# hardware-crackme.net
KiCad netlist of a schematic drawn in EAGLE
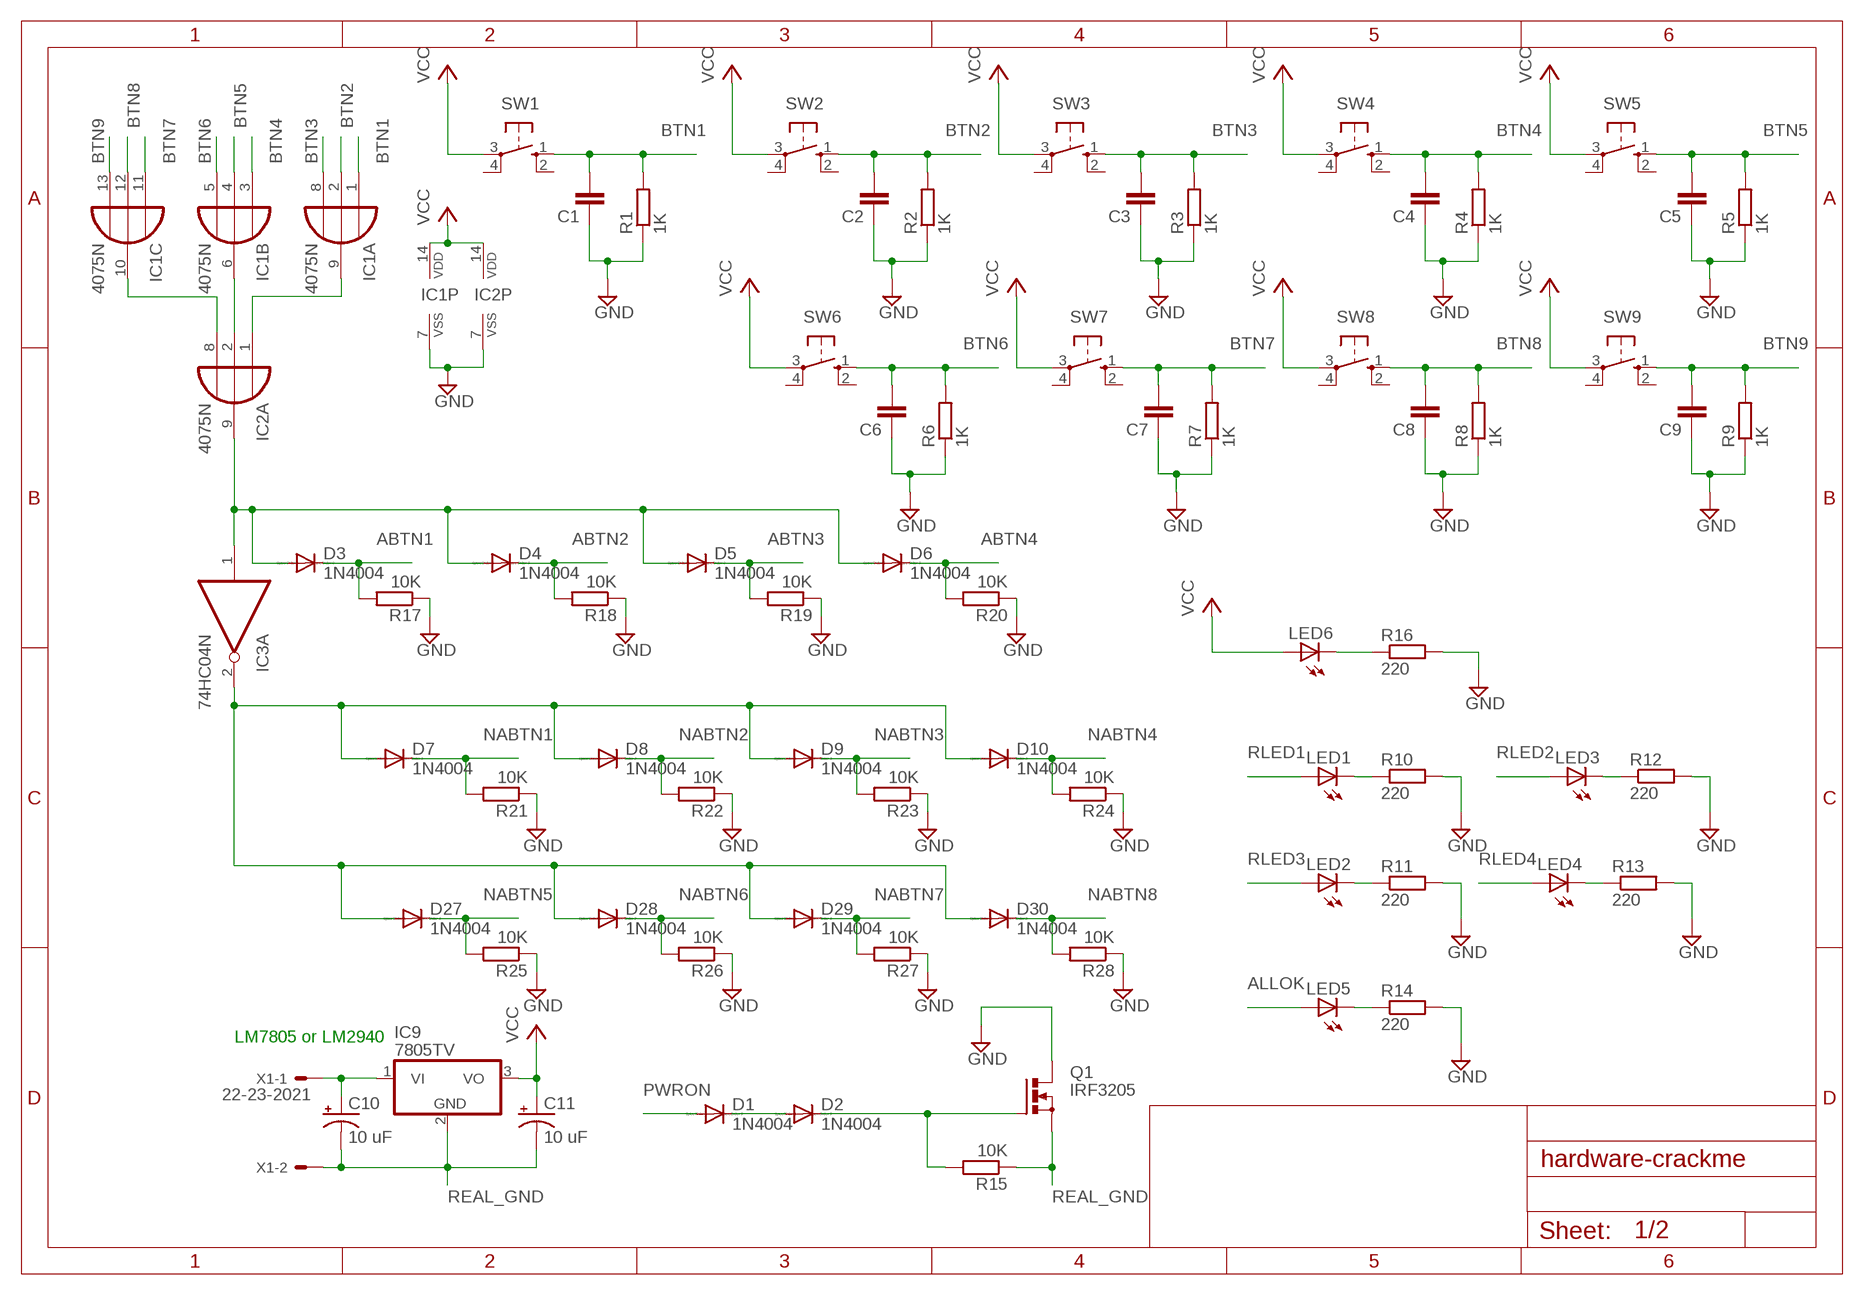
[diagram p0: schematic, sheet 1]
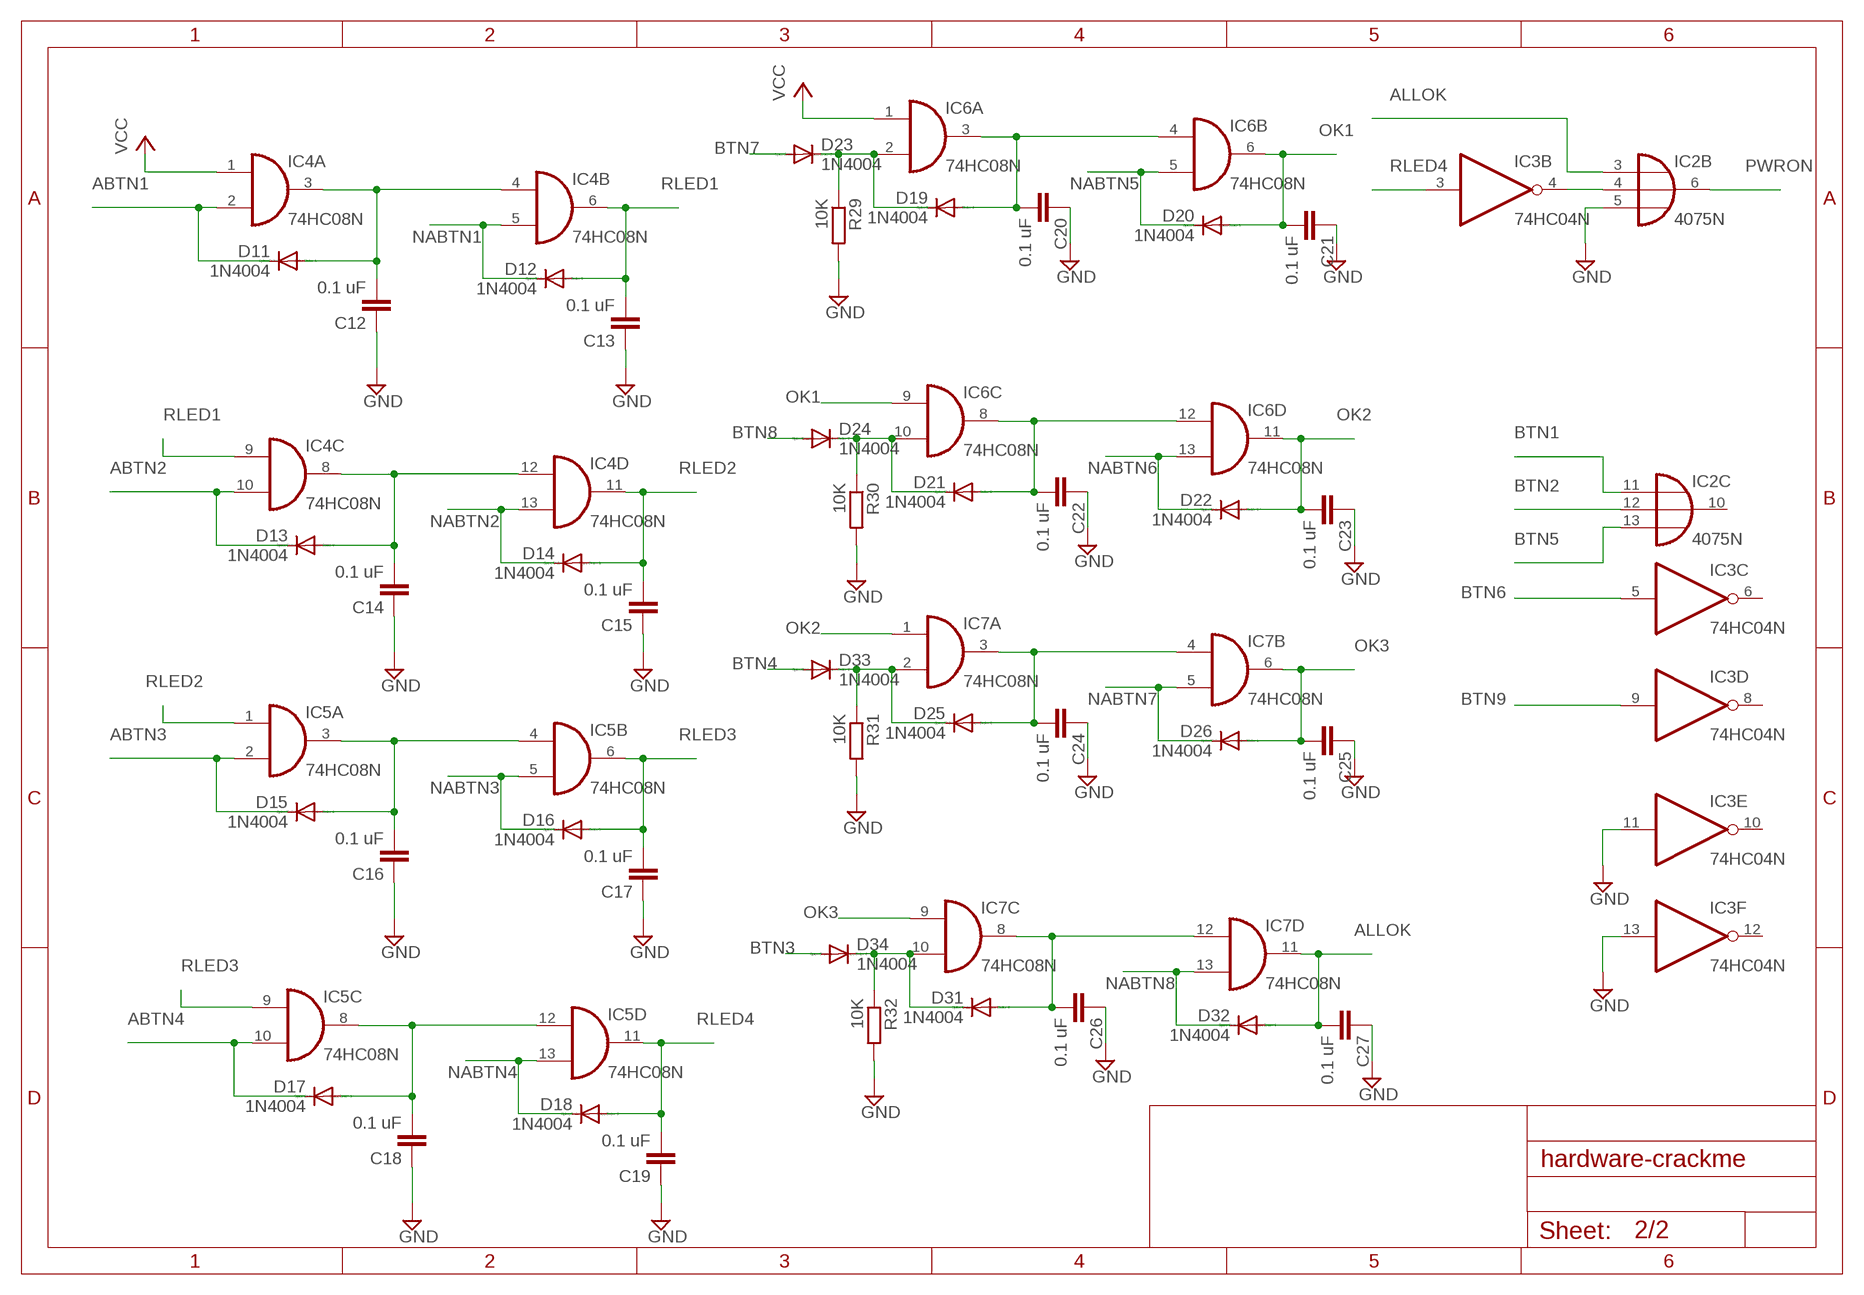
[diagram p1: schematic, sheet 2]

(export (version "E")
  (design (tool "Eeschema 10.0.6"))
  (components
    (comp (ref "C12")
      (value "0.1 uF")
      (footprint "eagle-import:C050-025X075")
      (libsource (lib "eagle-import") (part "C-EU050-025X075"))
    )
    (comp (ref "C13")
      (value "0.1 uF")
      (footprint "eagle-import:C050-025X075")
      (libsource (lib "eagle-import") (part "C-EU050-025X075"))
    )
    (comp (ref "C14")
      (value "0.1 uF")
      (footprint "eagle-import:C050-025X075")
      (libsource (lib "eagle-import") (part "C-EU050-025X075"))
    )
    (comp (ref "C15")
      (value "0.1 uF")
      (footprint "eagle-import:C050-025X075")
      (libsource (lib "eagle-import") (part "C-EU050-025X075"))
    )
    (comp (ref "C16")
      (value "0.1 uF")
      (footprint "eagle-import:C050-025X075")
      (libsource (lib "eagle-import") (part "C-EU050-025X075"))
    )
    (comp (ref "C17")
      (value "0.1 uF")
      (footprint "eagle-import:C050-025X075")
      (libsource (lib "eagle-import") (part "C-EU050-025X075"))
    )
    (comp (ref "C18")
      (value "0.1 uF")
      (footprint "eagle-import:C050-025X075")
      (libsource (lib "eagle-import") (part "C-EU050-025X075"))
    )
    (comp (ref "C19")
      (value "0.1 uF")
      (footprint "eagle-import:C050-025X075")
      (libsource (lib "eagle-import") (part "C-EU050-025X075"))
    )
    (comp (ref "C20")
      (value "0.1 uF")
      (footprint "eagle-import:C050-025X075")
      (libsource (lib "eagle-import") (part "C-EU050-025X075"))
    )
    (comp (ref "C21")
      (value "0.1 uF")
      (footprint "eagle-import:C050-025X075")
      (libsource (lib "eagle-import") (part "C-EU050-025X075"))
    )
    (comp (ref "C22")
      (value "0.1 uF")
      (footprint "eagle-import:C050-025X075")
      (libsource (lib "eagle-import") (part "C-EU050-025X075"))
    )
    (comp (ref "C23")
      (value "0.1 uF")
      (footprint "eagle-import:C050-025X075")
      (libsource (lib "eagle-import") (part "C-EU050-025X075"))
    )
    (comp (ref "C24")
      (value "0.1 uF")
      (footprint "eagle-import:C050-025X075")
      (libsource (lib "eagle-import") (part "C-EU050-025X075"))
    )
    (comp (ref "C25")
      (value "0.1 uF")
      (footprint "eagle-import:C050-025X075")
      (libsource (lib "eagle-import") (part "C-EU050-025X075"))
    )
    (comp (ref "C26")
      (value "0.1 uF")
      (footprint "eagle-import:C050-025X075")
      (libsource (lib "eagle-import") (part "C-EU050-025X075"))
    )
    (comp (ref "C27")
      (value "0.1 uF")
      (footprint "eagle-import:C050-025X075")
      (libsource (lib "eagle-import") (part "C-EU050-025X075"))
    )
    (comp (ref "D11")
      (value "1N4004")
      (footprint "eagle-import:DO41-10")
      (libsource (lib "eagle-import") (part "1N4004"))
    )
    (comp (ref "D12")
      (value "1N4004")
      (footprint "eagle-import:DO41-10")
      (libsource (lib "eagle-import") (part "1N4004"))
    )
    (comp (ref "D13")
      (value "1N4004")
      (footprint "eagle-import:DO41-10")
      (libsource (lib "eagle-import") (part "1N4004"))
    )
    (comp (ref "D14")
      (value "1N4004")
      (footprint "eagle-import:DO41-10")
      (libsource (lib "eagle-import") (part "1N4004"))
    )
    (comp (ref "D15")
      (value "1N4004")
      (footprint "eagle-import:DO41-10")
      (libsource (lib "eagle-import") (part "1N4004"))
    )
    (comp (ref "D16")
      (value "1N4004")
      (footprint "eagle-import:DO41-10")
      (libsource (lib "eagle-import") (part "1N4004"))
    )
    (comp (ref "D17")
      (value "1N4004")
      (footprint "eagle-import:DO41-10")
      (libsource (lib "eagle-import") (part "1N4004"))
    )
    (comp (ref "D18")
      (value "1N4004")
      (footprint "eagle-import:DO41-10")
      (libsource (lib "eagle-import") (part "1N4004"))
    )
    (comp (ref "D19")
      (value "1N4004")
      (footprint "eagle-import:DO41-10")
      (libsource (lib "eagle-import") (part "1N4004"))
    )
    (comp (ref "D20")
      (value "1N4004")
      (footprint "eagle-import:DO41-10")
      (libsource (lib "eagle-import") (part "1N4004"))
    )
    (comp (ref "D21")
      (value "1N4004")
      (footprint "eagle-import:DO41-10")
      (libsource (lib "eagle-import") (part "1N4004"))
    )
    (comp (ref "D22")
      (value "1N4004")
      (footprint "eagle-import:DO41-10")
      (libsource (lib "eagle-import") (part "1N4004"))
    )
    (comp (ref "D23")
      (value "1N4004")
      (footprint "eagle-import:DO41-10")
      (libsource (lib "eagle-import") (part "1N4004"))
    )
    (comp (ref "D24")
      (value "1N4004")
      (footprint "eagle-import:DO41-10")
      (libsource (lib "eagle-import") (part "1N4004"))
    )
    (comp (ref "D25")
      (value "1N4004")
      (footprint "eagle-import:DO41-10")
      (libsource (lib "eagle-import") (part "1N4004"))
    )
    (comp (ref "D26")
      (value "1N4004")
      (footprint "eagle-import:DO41-10")
      (libsource (lib "eagle-import") (part "1N4004"))
    )
    (comp (ref "D31")
      (value "1N4004")
      (footprint "eagle-import:DO41-10")
      (libsource (lib "eagle-import") (part "1N4004"))
    )
    (comp (ref "D32")
      (value "1N4004")
      (footprint "eagle-import:DO41-10")
      (libsource (lib "eagle-import") (part "1N4004"))
    )
    (comp (ref "D33")
      (value "1N4004")
      (footprint "eagle-import:DO41-10")
      (libsource (lib "eagle-import") (part "1N4004"))
    )
    (comp (ref "D34")
      (value "1N4004")
      (footprint "eagle-import:DO41-10")
      (libsource (lib "eagle-import") (part "1N4004"))
    )
    (comp (ref "IC2")
      (value "4075N")
      (footprint "eagle-import:DIL14")
      (libsource (lib "eagle-import") (part "4075N"))
    )
    (comp (ref "IC3")
      (value "74HC04N")
      (footprint "eagle-import:DIL14")
      (libsource (lib "eagle-import") (part "7404NHC"))
    )
    (comp (ref "IC4")
      (value "74HC08N")
      (footprint "eagle-import:DIL14")
      (libsource (lib "eagle-import") (part "7408NHC"))
    )
    (comp (ref "IC5")
      (value "74HC08N")
      (footprint "eagle-import:DIL14")
      (libsource (lib "eagle-import") (part "7408NHC"))
    )
    (comp (ref "IC6")
      (value "74HC08N")
      (footprint "eagle-import:DIL14")
      (libsource (lib "eagle-import") (part "7408NHC"))
    )
    (comp (ref "IC7")
      (value "74HC08N")
      (footprint "eagle-import:DIL14")
      (libsource (lib "eagle-import") (part "7408NHC"))
    )
    (comp (ref "R29")
      (value "10K")
      (footprint "eagle-import:0207_7")
      (libsource (lib "eagle-import") (part "R-EU_0207/7"))
    )
    (comp (ref "R30")
      (value "10K")
      (footprint "eagle-import:0207_7")
      (libsource (lib "eagle-import") (part "R-EU_0207/7"))
    )
    (comp (ref "R31")
      (value "10K")
      (footprint "eagle-import:0207_7")
      (libsource (lib "eagle-import") (part "R-EU_0207/7"))
    )
    (comp (ref "R32")
      (value "10K")
      (footprint "eagle-import:0207_7")
      (libsource (lib "eagle-import") (part "R-EU_0207/7"))
    )
    (comp (ref "C1")
      (value "C-EU050-025X075")
      (footprint "eagle-import:C050-025X075")
      (libsource (lib "eagle-import") (part "C-EU050-025X075"))
    )
    (comp (ref "C2")
      (value "C-EU050-025X075")
      (footprint "eagle-import:C050-025X075")
      (libsource (lib "eagle-import") (part "C-EU050-025X075"))
    )
    (comp (ref "C3")
      (value "C-EU050-025X075")
      (footprint "eagle-import:C050-025X075")
      (libsource (lib "eagle-import") (part "C-EU050-025X075"))
    )
    (comp (ref "C4")
      (value "C-EU050-025X075")
      (footprint "eagle-import:C050-025X075")
      (libsource (lib "eagle-import") (part "C-EU050-025X075"))
    )
    (comp (ref "C5")
      (value "C-EU050-025X075")
      (footprint "eagle-import:C050-025X075")
      (libsource (lib "eagle-import") (part "C-EU050-025X075"))
    )
    (comp (ref "C6")
      (value "C-EU050-025X075")
      (footprint "eagle-import:C050-025X075")
      (libsource (lib "eagle-import") (part "C-EU050-025X075"))
    )
    (comp (ref "C7")
      (value "C-EU050-025X075")
      (footprint "eagle-import:C050-025X075")
      (libsource (lib "eagle-import") (part "C-EU050-025X075"))
    )
    (comp (ref "C8")
      (value "C-EU050-025X075")
      (footprint "eagle-import:C050-025X075")
      (libsource (lib "eagle-import") (part "C-EU050-025X075"))
    )
    (comp (ref "C9")
      (value "C-EU050-025X075")
      (footprint "eagle-import:C050-025X075")
      (libsource (lib "eagle-import") (part "C-EU050-025X075"))
    )
    (comp (ref "C10")
      (value "10 uF")
      (footprint "eagle-import:E2,5-7")
      (libsource (lib "eagle-import") (part "CPOL-USE2.5-7"))
    )
    (comp (ref "C11")
      (value "10 uF")
      (footprint "eagle-import:E2,5-7")
      (libsource (lib "eagle-import") (part "CPOL-USE2.5-7"))
    )
    (comp (ref "D1")
      (value "1N4004")
      (footprint "eagle-import:DO41-10")
      (libsource (lib "eagle-import") (part "1N4004"))
    )
    (comp (ref "D2")
      (value "1N4004")
      (footprint "eagle-import:DO41-10")
      (libsource (lib "eagle-import") (part "1N4004"))
    )
    (comp (ref "D3")
      (value "1N4004")
      (footprint "eagle-import:DO41-10")
      (libsource (lib "eagle-import") (part "1N4004"))
    )
    (comp (ref "D4")
      (value "1N4004")
      (footprint "eagle-import:DO41-10")
      (libsource (lib "eagle-import") (part "1N4004"))
    )
    (comp (ref "D5")
      (value "1N4004")
      (footprint "eagle-import:DO41-10")
      (libsource (lib "eagle-import") (part "1N4004"))
    )
    (comp (ref "D6")
      (value "1N4004")
      (footprint "eagle-import:DO41-10")
      (libsource (lib "eagle-import") (part "1N4004"))
    )
    (comp (ref "D7")
      (value "1N4004")
      (footprint "eagle-import:DO41-10")
      (libsource (lib "eagle-import") (part "1N4004"))
    )
    (comp (ref "D8")
      (value "1N4004")
      (footprint "eagle-import:DO41-10")
      (libsource (lib "eagle-import") (part "1N4004"))
    )
    (comp (ref "D9")
      (value "1N4004")
      (footprint "eagle-import:DO41-10")
      (libsource (lib "eagle-import") (part "1N4004"))
    )
    (comp (ref "D10")
      (value "1N4004")
      (footprint "eagle-import:DO41-10")
      (libsource (lib "eagle-import") (part "1N4004"))
    )
    (comp (ref "D27")
      (value "1N4004")
      (footprint "eagle-import:DO41-10")
      (libsource (lib "eagle-import") (part "1N4004"))
    )
    (comp (ref "D28")
      (value "1N4004")
      (footprint "eagle-import:DO41-10")
      (libsource (lib "eagle-import") (part "1N4004"))
    )
    (comp (ref "D29")
      (value "1N4004")
      (footprint "eagle-import:DO41-10")
      (libsource (lib "eagle-import") (part "1N4004"))
    )
    (comp (ref "D30")
      (value "1N4004")
      (footprint "eagle-import:DO41-10")
      (libsource (lib "eagle-import") (part "1N4004"))
    )
    (comp (ref "IC1")
      (value "4075N")
      (footprint "eagle-import:DIL14")
      (fields (field (name "SUPPLY") "VCC"))
      (libsource (lib "eagle-import") (part "4075N"))
    )
    (comp (ref "IC9")
      (value "7805TV")
      (footprint "eagle-import:TO220V")
      (libsource (lib "eagle-import") (part "78TV05"))
    )
    (comp (ref "LED1")
      (value "LED5MM")
      (footprint "eagle-import:LED5MM")
      (libsource (lib "eagle-import") (part "LED5MM"))
    )
    (comp (ref "LED2")
      (value "LED5MM")
      (footprint "eagle-import:LED5MM")
      (libsource (lib "eagle-import") (part "LED5MM"))
    )
    (comp (ref "LED3")
      (value "LED5MM")
      (footprint "eagle-import:LED5MM")
      (libsource (lib "eagle-import") (part "LED5MM"))
    )
    (comp (ref "LED4")
      (value "LED5MM")
      (footprint "eagle-import:LED5MM")
      (libsource (lib "eagle-import") (part "LED5MM"))
    )
    (comp (ref "LED5")
      (value "LED5MM")
      (footprint "eagle-import:LED5MM")
      (libsource (lib "eagle-import") (part "LED5MM"))
    )
    (comp (ref "LED6")
      (value "LED5MM")
      (footprint "eagle-import:LED5MM")
      (libsource (lib "eagle-import") (part "LED5MM"))
    )
    (comp (ref "Q1")
      (value "IRF3205")
      (footprint "eagle-import:TO220BV")
      (libsource (lib "eagle-import") (part "PMOSFET_NTO220BV"))
    )
    (comp (ref "R1")
      (value "1K")
      (footprint "eagle-import:0207_7")
      (libsource (lib "eagle-import") (part "R-EU_0207/7"))
    )
    (comp (ref "R2")
      (value "1K")
      (footprint "eagle-import:0207_7")
      (libsource (lib "eagle-import") (part "R-EU_0207/7"))
    )
    (comp (ref "R3")
      (value "1K")
      (footprint "eagle-import:0207_7")
      (libsource (lib "eagle-import") (part "R-EU_0207/7"))
    )
    (comp (ref "R4")
      (value "1K")
      (footprint "eagle-import:0207_7")
      (libsource (lib "eagle-import") (part "R-EU_0207/7"))
    )
    (comp (ref "R5")
      (value "1K")
      (footprint "eagle-import:0207_7")
      (libsource (lib "eagle-import") (part "R-EU_0207/7"))
    )
    (comp (ref "R6")
      (value "1K")
      (footprint "eagle-import:0207_7")
      (libsource (lib "eagle-import") (part "R-EU_0207/7"))
    )
    (comp (ref "R7")
      (value "1K")
      (footprint "eagle-import:0207_7")
      (libsource (lib "eagle-import") (part "R-EU_0207/7"))
    )
    (comp (ref "R8")
      (value "1K")
      (footprint "eagle-import:0207_7")
      (libsource (lib "eagle-import") (part "R-EU_0207/7"))
    )
    (comp (ref "R9")
      (value "1K")
      (footprint "eagle-import:0207_7")
      (libsource (lib "eagle-import") (part "R-EU_0207/7"))
    )
    (comp (ref "R10")
      (value "220")
      (footprint "eagle-import:0207_7")
      (libsource (lib "eagle-import") (part "R-EU_0207/7"))
    )
    (comp (ref "R11")
      (value "220")
      (footprint "eagle-import:0207_7")
      (libsource (lib "eagle-import") (part "R-EU_0207/7"))
    )
    (comp (ref "R12")
      (value "220")
      (footprint "eagle-import:0207_7")
      (libsource (lib "eagle-import") (part "R-EU_0207/7"))
    )
    (comp (ref "R13")
      (value "220")
      (footprint "eagle-import:0207_7")
      (libsource (lib "eagle-import") (part "R-EU_0207/7"))
    )
    (comp (ref "R14")
      (value "220")
      (footprint "eagle-import:0207_7")
      (libsource (lib "eagle-import") (part "R-EU_0207/7"))
    )
    (comp (ref "R15")
      (value "10K")
      (footprint "eagle-import:0207_7")
      (libsource (lib "eagle-import") (part "R-EU_0207/7"))
    )
    (comp (ref "R16")
      (value "220")
      (footprint "eagle-import:0207_7")
      (libsource (lib "eagle-import") (part "R-EU_0207/7"))
    )
    (comp (ref "R17")
      (value "10K")
      (footprint "eagle-import:0207_7")
      (libsource (lib "eagle-import") (part "R-EU_0207/7"))
    )
    (comp (ref "R18")
      (value "10K")
      (footprint "eagle-import:0207_7")
      (libsource (lib "eagle-import") (part "R-EU_0207/7"))
    )
    (comp (ref "R19")
      (value "10K")
      (footprint "eagle-import:0207_7")
      (libsource (lib "eagle-import") (part "R-EU_0207/7"))
    )
    (comp (ref "R20")
      (value "10K")
      (footprint "eagle-import:0207_7")
      (libsource (lib "eagle-import") (part "R-EU_0207/7"))
    )
    (comp (ref "R21")
      (value "10K")
      (footprint "eagle-import:0207_7")
      (libsource (lib "eagle-import") (part "R-EU_0207/7"))
    )
    (comp (ref "R22")
      (value "10K")
      (footprint "eagle-import:0207_7")
      (libsource (lib "eagle-import") (part "R-EU_0207/7"))
    )
    (comp (ref "R23")
      (value "10K")
      (footprint "eagle-import:0207_7")
      (libsource (lib "eagle-import") (part "R-EU_0207/7"))
    )
    (comp (ref "R24")
      (value "10K")
      (footprint "eagle-import:0207_7")
      (libsource (lib "eagle-import") (part "R-EU_0207/7"))
    )
    (comp (ref "R25")
      (value "10K")
      (footprint "eagle-import:0207_7")
      (libsource (lib "eagle-import") (part "R-EU_0207/7"))
    )
    (comp (ref "R26")
      (value "10K")
      (footprint "eagle-import:0207_7")
      (libsource (lib "eagle-import") (part "R-EU_0207/7"))
    )
    (comp (ref "R27")
      (value "10K")
      (footprint "eagle-import:0207_7")
      (libsource (lib "eagle-import") (part "R-EU_0207/7"))
    )
    (comp (ref "R28")
      (value "10K")
      (footprint "eagle-import:0207_7")
      (libsource (lib "eagle-import") (part "R-EU_0207/7"))
    )
    (comp (ref "SW1")
      (value "10-XX")
      (footprint "eagle-import:B3F-10XX")
      (libsource (lib "eagle-import") (part "10-XX"))
    )
    (comp (ref "SW2")
      (value "10-XX")
      (footprint "eagle-import:B3F-10XX")
      (libsource (lib "eagle-import") (part "10-XX"))
    )
    (comp (ref "SW3")
      (value "10-XX")
      (footprint "eagle-import:B3F-10XX")
      (libsource (lib "eagle-import") (part "10-XX"))
    )
    (comp (ref "SW4")
      (value "10-XX")
      (footprint "eagle-import:B3F-10XX")
      (libsource (lib "eagle-import") (part "10-XX"))
    )
    (comp (ref "SW5")
      (value "10-XX")
      (footprint "eagle-import:B3F-10XX")
      (libsource (lib "eagle-import") (part "10-XX"))
    )
    (comp (ref "SW6")
      (value "10-XX")
      (footprint "eagle-import:B3F-10XX")
      (libsource (lib "eagle-import") (part "10-XX"))
    )
    (comp (ref "SW7")
      (value "10-XX")
      (footprint "eagle-import:B3F-10XX")
      (libsource (lib "eagle-import") (part "10-XX"))
    )
    (comp (ref "SW8")
      (value "10-XX")
      (footprint "eagle-import:B3F-10XX")
      (libsource (lib "eagle-import") (part "10-XX"))
    )
    (comp (ref "SW9")
      (value "10-XX")
      (footprint "eagle-import:B3F-10XX")
      (libsource (lib "eagle-import") (part "10-XX"))
    )
    (comp (ref "X1")
      (value "22-23-2021")
      (footprint "eagle-import:22-23-2021")
      (fields (field (name "MF") "MOLEX"))
      (libsource (lib "eagle-import") (part "22-23-2021"))
    )
  )
  (nets
    (net (code "1") (name "ABTN1") (class "Default")
      (node (ref "D11") (pin "C") (pinfunction "C_C") (pintype "passive"))
      (node (ref "D3") (pin "C") (pinfunction "C_C") (pintype "passive"))
      (node (ref "IC4") (pin "2") (pinfunction "I1_2") (pintype "input"))
      (node (ref "R17") (pin "2") (pinfunction "2_2") (pintype "passive"))
    )
    (net (code "2") (name "ABTN2") (class "Default")
      (node (ref "D13") (pin "C") (pinfunction "C_C") (pintype "passive"))
      (node (ref "D4") (pin "C") (pinfunction "C_C") (pintype "passive"))
      (node (ref "IC4") (pin "10") (pinfunction "I1_10") (pintype "input"))
      (node (ref "R18") (pin "2") (pinfunction "2_2") (pintype "passive"))
    )
    (net (code "3") (name "ABTN3") (class "Default")
      (node (ref "D15") (pin "C") (pinfunction "C_C") (pintype "passive"))
      (node (ref "D5") (pin "C") (pinfunction "C_C") (pintype "passive"))
      (node (ref "IC5") (pin "2") (pinfunction "I1_2") (pintype "input"))
      (node (ref "R19") (pin "2") (pinfunction "2_2") (pintype "passive"))
    )
    (net (code "4") (name "ABTN4") (class "Default")
      (node (ref "D17") (pin "C") (pinfunction "C_C") (pintype "passive"))
      (node (ref "D6") (pin "C") (pinfunction "C_C") (pintype "passive"))
      (node (ref "IC5") (pin "10") (pinfunction "I1_10") (pintype "input"))
      (node (ref "R20") (pin "2") (pinfunction "2_2") (pintype "passive"))
    )
    (net (code "5") (name "ALLOK") (class "Default")
      (node (ref "C27") (pin "2") (pinfunction "2_2") (pintype "passive"))
      (node (ref "D32") (pin "A") (pinfunction "A_A") (pintype "passive"))
      (node (ref "IC2") (pin "3") (pinfunction "I0_3") (pintype "input"))
      (node (ref "IC7") (pin "11") (pinfunction "O_11") (pintype "output"))
      (node (ref "LED5") (pin "A") (pinfunction "A_A") (pintype "passive"))
    )
    (net (code "6") (name "BTN1") (class "Default")
      (node (ref "C1") (pin "2") (pinfunction "2_2") (pintype "passive"))
      (node (ref "IC1") (pin "1") (pinfunction "I0_1") (pintype "input"))
      (node (ref "IC2") (pin "11") (pinfunction "I0_11") (pintype "input"))
      (node (ref "R1") (pin "2") (pinfunction "2_2") (pintype "passive"))
      (node (ref "SW1") (pin "1") (pinfunction "S_1") (pintype "passive"))
    )
    (net (code "7") (name "BTN2") (class "Default")
      (node (ref "C2") (pin "2") (pinfunction "2_2") (pintype "passive"))
      (node (ref "IC1") (pin "2") (pinfunction "I1_2") (pintype "input"))
      (node (ref "IC2") (pin "12") (pinfunction "I1_12") (pintype "input"))
      (node (ref "R2") (pin "2") (pinfunction "2_2") (pintype "passive"))
      (node (ref "SW2") (pin "1") (pinfunction "S_1") (pintype "passive"))
    )
    (net (code "8") (name "BTN3") (class "Default")
      (node (ref "C3") (pin "2") (pinfunction "2_2") (pintype "passive"))
      (node (ref "D34") (pin "A") (pinfunction "A_A") (pintype "passive"))
      (node (ref "IC1") (pin "8") (pinfunction "I2_8") (pintype "input"))
      (node (ref "R3") (pin "2") (pinfunction "2_2") (pintype "passive"))
      (node (ref "SW3") (pin "1") (pinfunction "S_1") (pintype "passive"))
    )
    (net (code "9") (name "BTN4") (class "Default")
      (node (ref "C4") (pin "2") (pinfunction "2_2") (pintype "passive"))
      (node (ref "D33") (pin "A") (pinfunction "A_A") (pintype "passive"))
      (node (ref "IC1") (pin "3") (pinfunction "I0_3") (pintype "input"))
      (node (ref "R4") (pin "2") (pinfunction "2_2") (pintype "passive"))
      (node (ref "SW4") (pin "1") (pinfunction "S_1") (pintype "passive"))
    )
    (net (code "10") (name "BTN5") (class "Default")
      (node (ref "C5") (pin "2") (pinfunction "2_2") (pintype "passive"))
      (node (ref "IC1") (pin "4") (pinfunction "I1_4") (pintype "input"))
      (node (ref "IC2") (pin "13") (pinfunction "I2_13") (pintype "input"))
      (node (ref "R5") (pin "2") (pinfunction "2_2") (pintype "passive"))
      (node (ref "SW5") (pin "1") (pinfunction "S_1") (pintype "passive"))
    )
    (net (code "11") (name "BTN6") (class "Default")
      (node (ref "C6") (pin "2") (pinfunction "2_2") (pintype "passive"))
      (node (ref "IC1") (pin "5") (pinfunction "I2_5") (pintype "input"))
      (node (ref "IC3") (pin "5") (pinfunction "I_5") (pintype "input"))
      (node (ref "R6") (pin "2") (pinfunction "2_2") (pintype "passive"))
      (node (ref "SW6") (pin "1") (pinfunction "S_1") (pintype "passive"))
    )
    (net (code "12") (name "BTN7") (class "Default")
      (node (ref "C7") (pin "2") (pinfunction "2_2") (pintype "passive"))
      (node (ref "D23") (pin "A") (pinfunction "A_A") (pintype "passive"))
      (node (ref "IC1") (pin "11") (pinfunction "I0_11") (pintype "input"))
      (node (ref "R7") (pin "2") (pinfunction "2_2") (pintype "passive"))
      (node (ref "SW7") (pin "1") (pinfunction "S_1") (pintype "passive"))
    )
    (net (code "13") (name "BTN8") (class "Default")
      (node (ref "C8") (pin "2") (pinfunction "2_2") (pintype "passive"))
      (node (ref "D24") (pin "A") (pinfunction "A_A") (pintype "passive"))
      (node (ref "IC1") (pin "12") (pinfunction "I1_12") (pintype "input"))
      (node (ref "R8") (pin "2") (pinfunction "2_2") (pintype "passive"))
      (node (ref "SW8") (pin "1") (pinfunction "S_1") (pintype "passive"))
    )
    (net (code "14") (name "BTN9") (class "Default")
      (node (ref "C9") (pin "2") (pinfunction "2_2") (pintype "passive"))
      (node (ref "IC1") (pin "13") (pinfunction "I2_13") (pintype "input"))
      (node (ref "IC3") (pin "9") (pinfunction "I_9") (pintype "input"))
      (node (ref "R9") (pin "2") (pinfunction "2_2") (pintype "passive"))
      (node (ref "SW9") (pin "1") (pinfunction "S_1") (pintype "passive"))
    )
    (net (code "15") (name "GND") (class "Default")
      (node (ref "C1") (pin "1") (pinfunction "1_1") (pintype "passive"))
      (node (ref "C12") (pin "1") (pinfunction "1_1") (pintype "passive"))
      (node (ref "C13") (pin "1") (pinfunction "1_1") (pintype "passive"))
      (node (ref "C14") (pin "1") (pinfunction "1_1") (pintype "passive"))
      (node (ref "C15") (pin "1") (pinfunction "1_1") (pintype "passive"))
      (node (ref "C16") (pin "1") (pinfunction "1_1") (pintype "passive"))
      (node (ref "C17") (pin "1") (pinfunction "1_1") (pintype "passive"))
      (node (ref "C18") (pin "1") (pinfunction "1_1") (pintype "passive"))
      (node (ref "C19") (pin "1") (pinfunction "1_1") (pintype "passive"))
      (node (ref "C2") (pin "1") (pinfunction "1_1") (pintype "passive"))
      (node (ref "C20") (pin "1") (pinfunction "1_1") (pintype "passive"))
      (node (ref "C21") (pin "1") (pinfunction "1_1") (pintype "passive"))
      (node (ref "C22") (pin "1") (pinfunction "1_1") (pintype "passive"))
      (node (ref "C23") (pin "1") (pinfunction "1_1") (pintype "passive"))
      (node (ref "C24") (pin "1") (pinfunction "1_1") (pintype "passive"))
      (node (ref "C25") (pin "1") (pinfunction "1_1") (pintype "passive"))
      (node (ref "C26") (pin "1") (pinfunction "1_1") (pintype "passive"))
      (node (ref "C27") (pin "1") (pinfunction "1_1") (pintype "passive"))
      (node (ref "C3") (pin "1") (pinfunction "1_1") (pintype "passive"))
      (node (ref "C4") (pin "1") (pinfunction "1_1") (pintype "passive"))
      (node (ref "C5") (pin "1") (pinfunction "1_1") (pintype "passive"))
      (node (ref "C6") (pin "1") (pinfunction "1_1") (pintype "passive"))
      (node (ref "C7") (pin "1") (pinfunction "1_1") (pintype "passive"))
      (node (ref "C8") (pin "1") (pinfunction "1_1") (pintype "passive"))
      (node (ref "C9") (pin "1") (pinfunction "1_1") (pintype "passive"))
      (node (ref "IC1") (pin "7") (pinfunction "VSS_7") (pintype "power_in"))
      (node (ref "IC2") (pin "5") (pinfunction "I2_5") (pintype "input"))
      (node (ref "IC2") (pin "7") (pinfunction "VSS_7") (pintype "power_in"))
      (node (ref "IC3") (pin "11") (pinfunction "I_11") (pintype "input"))
      (node (ref "IC3") (pin "13") (pinfunction "I_13") (pintype "input"))
      (node (ref "Q1") (pin "D") (pinfunction "D_D") (pintype "passive"))
      (node (ref "R1") (pin "1") (pinfunction "1_1") (pintype "passive"))
      (node (ref "R10") (pin "2") (pinfunction "2_2") (pintype "passive"))
      (node (ref "R11") (pin "2") (pinfunction "2_2") (pintype "passive"))
      (node (ref "R12") (pin "2") (pinfunction "2_2") (pintype "passive"))
      (node (ref "R13") (pin "2") (pinfunction "2_2") (pintype "passive"))
      (node (ref "R14") (pin "2") (pinfunction "2_2") (pintype "passive"))
      (node (ref "R16") (pin "2") (pinfunction "2_2") (pintype "passive"))
      (node (ref "R17") (pin "1") (pinfunction "1_1") (pintype "passive"))
      (node (ref "R18") (pin "1") (pinfunction "1_1") (pintype "passive"))
      (node (ref "R19") (pin "1") (pinfunction "1_1") (pintype "passive"))
      (node (ref "R2") (pin "1") (pinfunction "1_1") (pintype "passive"))
      (node (ref "R20") (pin "1") (pinfunction "1_1") (pintype "passive"))
      (node (ref "R21") (pin "1") (pinfunction "1_1") (pintype "passive"))
      (node (ref "R22") (pin "1") (pinfunction "1_1") (pintype "passive"))
      (node (ref "R23") (pin "1") (pinfunction "1_1") (pintype "passive"))
      (node (ref "R24") (pin "1") (pinfunction "1_1") (pintype "passive"))
      (node (ref "R25") (pin "1") (pinfunction "1_1") (pintype "passive"))
      (node (ref "R26") (pin "1") (pinfunction "1_1") (pintype "passive"))
      (node (ref "R27") (pin "1") (pinfunction "1_1") (pintype "passive"))
      (node (ref "R28") (pin "1") (pinfunction "1_1") (pintype "passive"))
      (node (ref "R29") (pin "2") (pinfunction "2_2") (pintype "passive"))
      (node (ref "R3") (pin "1") (pinfunction "1_1") (pintype "passive"))
      (node (ref "R30") (pin "2") (pinfunction "2_2") (pintype "passive"))
      (node (ref "R31") (pin "2") (pinfunction "2_2") (pintype "passive"))
      (node (ref "R32") (pin "2") (pinfunction "2_2") (pintype "passive"))
      (node (ref "R4") (pin "1") (pinfunction "1_1") (pintype "passive"))
      (node (ref "R5") (pin "1") (pinfunction "1_1") (pintype "passive"))
      (node (ref "R6") (pin "1") (pinfunction "1_1") (pintype "passive"))
      (node (ref "R7") (pin "1") (pinfunction "1_1") (pintype "passive"))
      (node (ref "R8") (pin "1") (pinfunction "1_1") (pintype "passive"))
      (node (ref "R9") (pin "1") (pinfunction "1_1") (pintype "passive"))
    )
    (net (code "16") (name "NABTN1") (class "Default")
      (node (ref "D12") (pin "C") (pinfunction "C_C") (pintype "passive"))
      (node (ref "D7") (pin "C") (pinfunction "C_C") (pintype "passive"))
      (node (ref "IC4") (pin "5") (pinfunction "I1_5") (pintype "input"))
      (node (ref "R21") (pin "2") (pinfunction "2_2") (pintype "passive"))
    )
    (net (code "17") (name "NABTN2") (class "Default")
      (node (ref "D14") (pin "C") (pinfunction "C_C") (pintype "passive"))
      (node (ref "D8") (pin "C") (pinfunction "C_C") (pintype "passive"))
      (node (ref "IC4") (pin "13") (pinfunction "I1_13") (pintype "input"))
      (node (ref "R22") (pin "2") (pinfunction "2_2") (pintype "passive"))
    )
    (net (code "18") (name "NABTN3") (class "Default")
      (node (ref "D16") (pin "C") (pinfunction "C_C") (pintype "passive"))
      (node (ref "D9") (pin "C") (pinfunction "C_C") (pintype "passive"))
      (node (ref "IC5") (pin "5") (pinfunction "I1_5") (pintype "input"))
      (node (ref "R23") (pin "2") (pinfunction "2_2") (pintype "passive"))
    )
    (net (code "19") (name "NABTN4") (class "Default")
      (node (ref "D10") (pin "C") (pinfunction "C_C") (pintype "passive"))
      (node (ref "D18") (pin "C") (pinfunction "C_C") (pintype "passive"))
      (node (ref "IC5") (pin "13") (pinfunction "I1_13") (pintype "input"))
      (node (ref "R24") (pin "2") (pinfunction "2_2") (pintype "passive"))
    )
    (net (code "20") (name "NABTN5") (class "Default")
      (node (ref "D20") (pin "C") (pinfunction "C_C") (pintype "passive"))
      (node (ref "D27") (pin "C") (pinfunction "C_C") (pintype "passive"))
      (node (ref "IC6") (pin "5") (pinfunction "I1_5") (pintype "input"))
      (node (ref "R25") (pin "2") (pinfunction "2_2") (pintype "passive"))
    )
    (net (code "21") (name "NABTN6") (class "Default")
      (node (ref "D22") (pin "C") (pinfunction "C_C") (pintype "passive"))
      (node (ref "D28") (pin "C") (pinfunction "C_C") (pintype "passive"))
      (node (ref "IC6") (pin "13") (pinfunction "I1_13") (pintype "input"))
      (node (ref "R26") (pin "2") (pinfunction "2_2") (pintype "passive"))
    )
    (net (code "22") (name "NABTN7") (class "Default")
      (node (ref "D26") (pin "C") (pinfunction "C_C") (pintype "passive"))
      (node (ref "D29") (pin "C") (pinfunction "C_C") (pintype "passive"))
      (node (ref "IC7") (pin "5") (pinfunction "I1_5") (pintype "input"))
      (node (ref "R27") (pin "2") (pinfunction "2_2") (pintype "passive"))
    )
    (net (code "23") (name "NABTN8") (class "Default")
      (node (ref "D30") (pin "C") (pinfunction "C_C") (pintype "passive"))
      (node (ref "D32") (pin "C") (pinfunction "C_C") (pintype "passive"))
      (node (ref "IC7") (pin "13") (pinfunction "I1_13") (pintype "input"))
      (node (ref "R28") (pin "2") (pinfunction "2_2") (pintype "passive"))
    )
    (net (code "24") (name "Net-(D1-PadC)") (class "Default")
      (node (ref "D1") (pin "C") (pinfunction "C_C") (pintype "passive"))
      (node (ref "D2") (pin "A") (pinfunction "A_A") (pintype "passive"))
    )
    (net (code "25") (name "Net-(D2-PadC)") (class "Default")
      (node (ref "D2") (pin "C") (pinfunction "C_C") (pintype "passive"))
      (node (ref "Q1") (pin "G") (pinfunction "G_G") (pintype "passive"))
      (node (ref "R15") (pin "2") (pinfunction "2_2") (pintype "passive"))
    )
    (net (code "26") (name "Net-(IC1A-O)") (class "Default")
      (node (ref "IC1") (pin "9") (pinfunction "O_9") (pintype "output"))
      (node (ref "IC2") (pin "1") (pinfunction "I0_1") (pintype "input"))
    )
    (net (code "27") (name "Net-(IC1B-O)") (class "Default")
      (node (ref "IC1") (pin "6") (pinfunction "O_6") (pintype "output"))
      (node (ref "IC2") (pin "2") (pinfunction "I1_2") (pintype "input"))
    )
    (net (code "28") (name "Net-(IC1C-O)") (class "Default")
      (node (ref "IC1") (pin "10") (pinfunction "O_10") (pintype "output"))
      (node (ref "IC2") (pin "8") (pinfunction "I2_8") (pintype "input"))
    )
    (net (code "29") (name "Net-(IC2A-O)") (class "Default")
      (node (ref "D3") (pin "A") (pinfunction "A_A") (pintype "passive"))
      (node (ref "D4") (pin "A") (pinfunction "A_A") (pintype "passive"))
      (node (ref "D5") (pin "A") (pinfunction "A_A") (pintype "passive"))
      (node (ref "D6") (pin "A") (pinfunction "A_A") (pintype "passive"))
      (node (ref "IC2") (pin "9") (pinfunction "O_9") (pintype "output"))
      (node (ref "IC3") (pin "1") (pinfunction "I_1") (pintype "input"))
    )
    (net (code "30") (name "Net-(IC2B-I1)") (class "Default")
      (node (ref "IC2") (pin "4") (pinfunction "I1_4") (pintype "input"))
      (node (ref "IC3") (pin "4") (pinfunction "O_4") (pintype "output"))
    )
    (net (code "31") (name "Net-(IC3A-O)") (class "Default")
      (node (ref "D10") (pin "A") (pinfunction "A_A") (pintype "passive"))
      (node (ref "D27") (pin "A") (pinfunction "A_A") (pintype "passive"))
      (node (ref "D28") (pin "A") (pinfunction "A_A") (pintype "passive"))
      (node (ref "D29") (pin "A") (pinfunction "A_A") (pintype "passive"))
      (node (ref "D30") (pin "A") (pinfunction "A_A") (pintype "passive"))
      (node (ref "D7") (pin "A") (pinfunction "A_A") (pintype "passive"))
      (node (ref "D8") (pin "A") (pinfunction "A_A") (pintype "passive"))
      (node (ref "D9") (pin "A") (pinfunction "A_A") (pintype "passive"))
      (node (ref "IC3") (pin "2") (pinfunction "O_2") (pintype "output"))
    )
    (net (code "32") (name "Net-(IC4A-O)") (class "Default")
      (node (ref "C12") (pin "2") (pinfunction "2_2") (pintype "passive"))
      (node (ref "D11") (pin "A") (pinfunction "A_A") (pintype "passive"))
      (node (ref "IC4") (pin "3") (pinfunction "O_3") (pintype "output"))
      (node (ref "IC4") (pin "4") (pinfunction "I0_4") (pintype "input"))
    )
    (net (code "33") (name "Net-(IC4C-O)") (class "Default")
      (node (ref "C14") (pin "2") (pinfunction "2_2") (pintype "passive"))
      (node (ref "D13") (pin "A") (pinfunction "A_A") (pintype "passive"))
      (node (ref "IC4") (pin "12") (pinfunction "I0_12") (pintype "input"))
      (node (ref "IC4") (pin "8") (pinfunction "O_8") (pintype "output"))
    )
    (net (code "34") (name "Net-(IC5A-O)") (class "Default")
      (node (ref "C16") (pin "2") (pinfunction "2_2") (pintype "passive"))
      (node (ref "D15") (pin "A") (pinfunction "A_A") (pintype "passive"))
      (node (ref "IC5") (pin "3") (pinfunction "O_3") (pintype "output"))
      (node (ref "IC5") (pin "4") (pinfunction "I0_4") (pintype "input"))
    )
    (net (code "35") (name "Net-(IC5C-O)") (class "Default")
      (node (ref "C18") (pin "2") (pinfunction "2_2") (pintype "passive"))
      (node (ref "D17") (pin "A") (pinfunction "A_A") (pintype "passive"))
      (node (ref "IC5") (pin "12") (pinfunction "I0_12") (pintype "input"))
      (node (ref "IC5") (pin "8") (pinfunction "O_8") (pintype "output"))
    )
    (net (code "36") (name "Net-(IC6A-I1)") (class "Default")
      (node (ref "D19") (pin "C") (pinfunction "C_C") (pintype "passive"))
      (node (ref "D23") (pin "C") (pinfunction "C_C") (pintype "passive"))
      (node (ref "IC6") (pin "2") (pinfunction "I1_2") (pintype "input"))
      (node (ref "R29") (pin "1") (pinfunction "1_1") (pintype "passive"))
    )
    (net (code "37") (name "Net-(IC6A-O)") (class "Default")
      (node (ref "C20") (pin "2") (pinfunction "2_2") (pintype "passive"))
      (node (ref "D19") (pin "A") (pinfunction "A_A") (pintype "passive"))
      (node (ref "IC6") (pin "3") (pinfunction "O_3") (pintype "output"))
      (node (ref "IC6") (pin "4") (pinfunction "I0_4") (pintype "input"))
    )
    (net (code "38") (name "Net-(IC6C-I1)") (class "Default")
      (node (ref "D21") (pin "C") (pinfunction "C_C") (pintype "passive"))
      (node (ref "D24") (pin "C") (pinfunction "C_C") (pintype "passive"))
      (node (ref "IC6") (pin "10") (pinfunction "I1_10") (pintype "input"))
      (node (ref "R30") (pin "1") (pinfunction "1_1") (pintype "passive"))
    )
    (net (code "39") (name "Net-(IC6C-O)") (class "Default")
      (node (ref "C22") (pin "2") (pinfunction "2_2") (pintype "passive"))
      (node (ref "D21") (pin "A") (pinfunction "A_A") (pintype "passive"))
      (node (ref "IC6") (pin "12") (pinfunction "I0_12") (pintype "input"))
      (node (ref "IC6") (pin "8") (pinfunction "O_8") (pintype "output"))
    )
    (net (code "40") (name "Net-(IC7A-I1)") (class "Default")
      (node (ref "D25") (pin "C") (pinfunction "C_C") (pintype "passive"))
      (node (ref "D33") (pin "C") (pinfunction "C_C") (pintype "passive"))
      (node (ref "IC7") (pin "2") (pinfunction "I1_2") (pintype "input"))
      (node (ref "R31") (pin "1") (pinfunction "1_1") (pintype "passive"))
    )
    (net (code "41") (name "Net-(IC7A-O)") (class "Default")
      (node (ref "C24") (pin "2") (pinfunction "2_2") (pintype "passive"))
      (node (ref "D25") (pin "A") (pinfunction "A_A") (pintype "passive"))
      (node (ref "IC7") (pin "3") (pinfunction "O_3") (pintype "output"))
      (node (ref "IC7") (pin "4") (pinfunction "I0_4") (pintype "input"))
    )
    (net (code "42") (name "Net-(IC7C-I1)") (class "Default")
      (node (ref "D31") (pin "C") (pinfunction "C_C") (pintype "passive"))
      (node (ref "D34") (pin "C") (pinfunction "C_C") (pintype "passive"))
      (node (ref "IC7") (pin "10") (pinfunction "I1_10") (pintype "input"))
      (node (ref "R32") (pin "1") (pinfunction "1_1") (pintype "passive"))
    )
    (net (code "43") (name "Net-(IC7C-O)") (class "Default")
      (node (ref "C26") (pin "2") (pinfunction "2_2") (pintype "passive"))
      (node (ref "D31") (pin "A") (pinfunction "A_A") (pintype "passive"))
      (node (ref "IC7") (pin "12") (pinfunction "I0_12") (pintype "input"))
      (node (ref "IC7") (pin "8") (pinfunction "O_8") (pintype "output"))
    )
    (net (code "44") (name "Net-(IC9-VI)") (class "Default")
      (node (ref "C10") (pin "+") (pinfunction "+_+") (pintype "passive"))
      (node (ref "IC9") (pin "1") (pinfunction "VI_1") (pintype "input"))
      (node (ref "X1") (pin "1") (pinfunction "S_1") (pintype "passive"))
    )
    (net (code "45") (name "Net-(LED1-C)") (class "Default")
      (node (ref "LED1") (pin "K") (pinfunction "C_K") (pintype "passive"))
      (node (ref "R10") (pin "1") (pinfunction "1_1") (pintype "passive"))
    )
    (net (code "46") (name "Net-(LED2-C)") (class "Default")
      (node (ref "LED2") (pin "K") (pinfunction "C_K") (pintype "passive"))
      (node (ref "R11") (pin "1") (pinfunction "1_1") (pintype "passive"))
    )
    (net (code "47") (name "Net-(LED3-C)") (class "Default")
      (node (ref "LED3") (pin "K") (pinfunction "C_K") (pintype "passive"))
      (node (ref "R12") (pin "1") (pinfunction "1_1") (pintype "passive"))
    )
    (net (code "48") (name "Net-(LED4-C)") (class "Default")
      (node (ref "LED4") (pin "K") (pinfunction "C_K") (pintype "passive"))
      (node (ref "R13") (pin "1") (pinfunction "1_1") (pintype "passive"))
    )
    (net (code "49") (name "Net-(LED5-C)") (class "Default")
      (node (ref "LED5") (pin "K") (pinfunction "C_K") (pintype "passive"))
      (node (ref "R14") (pin "1") (pinfunction "1_1") (pintype "passive"))
    )
    (net (code "50") (name "Net-(LED6-C)") (class "Default")
      (node (ref "LED6") (pin "K") (pinfunction "C_K") (pintype "passive"))
      (node (ref "R16") (pin "1") (pinfunction "1_1") (pintype "passive"))
    )
    (net (code "51") (name "OK1") (class "Default")
      (node (ref "C21") (pin "2") (pinfunction "2_2") (pintype "passive"))
      (node (ref "D20") (pin "A") (pinfunction "A_A") (pintype "passive"))
      (node (ref "IC6") (pin "6") (pinfunction "O_6") (pintype "output"))
      (node (ref "IC6") (pin "9") (pinfunction "I0_9") (pintype "input"))
    )
    (net (code "52") (name "OK2") (class "Default")
      (node (ref "C23") (pin "2") (pinfunction "2_2") (pintype "passive"))
      (node (ref "D22") (pin "A") (pinfunction "A_A") (pintype "passive"))
      (node (ref "IC6") (pin "11") (pinfunction "O_11") (pintype "output"))
      (node (ref "IC7") (pin "1") (pinfunction "I0_1") (pintype "input"))
    )
    (net (code "53") (name "OK3") (class "Default")
      (node (ref "C25") (pin "2") (pinfunction "2_2") (pintype "passive"))
      (node (ref "D26") (pin "A") (pinfunction "A_A") (pintype "passive"))
      (node (ref "IC7") (pin "6") (pinfunction "O_6") (pintype "output"))
      (node (ref "IC7") (pin "9") (pinfunction "I0_9") (pintype "input"))
    )
    (net (code "54") (name "PWRON") (class "Default")
      (node (ref "D1") (pin "A") (pinfunction "A_A") (pintype "passive"))
      (node (ref "IC2") (pin "6") (pinfunction "O_6") (pintype "output"))
    )
    (net (code "55") (name "REAL_GND") (class "Default")
      (node (ref "C10") (pin "-") (pinfunction "-_-") (pintype "passive"))
      (node (ref "C11") (pin "-") (pinfunction "-_-") (pintype "passive"))
      (node (ref "IC9") (pin "2") (pinfunction "GND_2") (pintype "passive"))
      (node (ref "Q1") (pin "S") (pinfunction "S_S") (pintype "passive"))
      (node (ref "R15") (pin "1") (pinfunction "1_1") (pintype "passive"))
      (node (ref "X1") (pin "2") (pinfunction "S_2") (pintype "passive"))
    )
    (net (code "56") (name "RLED1") (class "Default")
      (node (ref "C13") (pin "2") (pinfunction "2_2") (pintype "passive"))
      (node (ref "D12") (pin "A") (pinfunction "A_A") (pintype "passive"))
      (node (ref "IC4") (pin "6") (pinfunction "O_6") (pintype "output"))
      (node (ref "IC4") (pin "9") (pinfunction "I0_9") (pintype "input"))
      (node (ref "LED1") (pin "A") (pinfunction "A_A") (pintype "passive"))
    )
    (net (code "57") (name "RLED2") (class "Default")
      (node (ref "C15") (pin "2") (pinfunction "2_2") (pintype "passive"))
      (node (ref "D14") (pin "A") (pinfunction "A_A") (pintype "passive"))
      (node (ref "IC4") (pin "11") (pinfunction "O_11") (pintype "output"))
      (node (ref "IC5") (pin "1") (pinfunction "I0_1") (pintype "input"))
      (node (ref "LED3") (pin "A") (pinfunction "A_A") (pintype "passive"))
    )
    (net (code "58") (name "RLED3") (class "Default")
      (node (ref "C17") (pin "2") (pinfunction "2_2") (pintype "passive"))
      (node (ref "D16") (pin "A") (pinfunction "A_A") (pintype "passive"))
      (node (ref "IC5") (pin "6") (pinfunction "O_6") (pintype "output"))
      (node (ref "IC5") (pin "9") (pinfunction "I0_9") (pintype "input"))
      (node (ref "LED2") (pin "A") (pinfunction "A_A") (pintype "passive"))
    )
    (net (code "59") (name "RLED4") (class "Default")
      (node (ref "C19") (pin "2") (pinfunction "2_2") (pintype "passive"))
      (node (ref "D18") (pin "A") (pinfunction "A_A") (pintype "passive"))
      (node (ref "IC3") (pin "3") (pinfunction "I_3") (pintype "input"))
      (node (ref "IC5") (pin "11") (pinfunction "O_11") (pintype "output"))
      (node (ref "LED4") (pin "A") (pinfunction "A_A") (pintype "passive"))
    )
    (net (code "60") (name "VCC") (class "Default")
      (node (ref "C11") (pin "+") (pinfunction "+_+") (pintype "passive"))
      (node (ref "IC1") (pin "14") (pinfunction "VDD_14") (pintype "power_in"))
      (node (ref "IC2") (pin "14") (pinfunction "VDD_14") (pintype "power_in"))
      (node (ref "IC4") (pin "1") (pinfunction "I0_1") (pintype "input"))
      (node (ref "IC6") (pin "1") (pinfunction "I0_1") (pintype "input"))
      (node (ref "IC9") (pin "3") (pinfunction "VO_3") (pintype "passive"))
      (node (ref "LED6") (pin "A") (pinfunction "A_A") (pintype "passive"))
      (node (ref "SW1") (pin "3") (pinfunction "P_3") (pintype "passive"))
      (node (ref "SW2") (pin "3") (pinfunction "P_3") (pintype "passive"))
      (node (ref "SW3") (pin "3") (pinfunction "P_3") (pintype "passive"))
      (node (ref "SW4") (pin "3") (pinfunction "P_3") (pintype "passive"))
      (node (ref "SW5") (pin "3") (pinfunction "P_3") (pintype "passive"))
      (node (ref "SW6") (pin "3") (pinfunction "P_3") (pintype "passive"))
      (node (ref "SW7") (pin "3") (pinfunction "P_3") (pintype "passive"))
      (node (ref "SW8") (pin "3") (pinfunction "P_3") (pintype "passive"))
      (node (ref "SW9") (pin "3") (pinfunction "P_3") (pintype "passive"))
    )
    (net (code "61") (name "unconnected-(IC2C-O-Pad10)") (class "Default")
      (node (ref "IC2") (pin "10") (pinfunction "O_10") (pintype "output"))
    )
    (net (code "62") (name "unconnected-(IC3C-O-Pad6)") (class "Default")
      (node (ref "IC3") (pin "6") (pinfunction "O_6") (pintype "output"))
    )
    (net (code "63") (name "unconnected-(IC3D-O-Pad8)") (class "Default")
      (node (ref "IC3") (pin "8") (pinfunction "O_8") (pintype "output"))
    )
    (net (code "64") (name "unconnected-(IC3E-O-Pad10)") (class "Default")
      (node (ref "IC3") (pin "10") (pinfunction "O_10") (pintype "output"))
    )
    (net (code "65") (name "unconnected-(IC3F-O-Pad12)") (class "Default")
      (node (ref "IC3") (pin "12") (pinfunction "O_12") (pintype "output"))
    )
    (net (code "66") (name "unconnected-(SW1-P1-Pad4)") (class "Default")
      (node (ref "SW1") (pin "4") (pinfunction "P1_4") (pintype "passive"))
    )
    (net (code "67") (name "unconnected-(SW1-S1-Pad2)") (class "Default")
      (node (ref "SW1") (pin "2") (pinfunction "S1_2") (pintype "passive"))
    )
    (net (code "68") (name "unconnected-(SW2-P1-Pad4)") (class "Default")
      (node (ref "SW2") (pin "4") (pinfunction "P1_4") (pintype "passive"))
    )
    (net (code "69") (name "unconnected-(SW2-S1-Pad2)") (class "Default")
      (node (ref "SW2") (pin "2") (pinfunction "S1_2") (pintype "passive"))
    )
    (net (code "70") (name "unconnected-(SW3-P1-Pad4)") (class "Default")
      (node (ref "SW3") (pin "4") (pinfunction "P1_4") (pintype "passive"))
    )
    (net (code "71") (name "unconnected-(SW3-S1-Pad2)") (class "Default")
      (node (ref "SW3") (pin "2") (pinfunction "S1_2") (pintype "passive"))
    )
    (net (code "72") (name "unconnected-(SW4-P1-Pad4)") (class "Default")
      (node (ref "SW4") (pin "4") (pinfunction "P1_4") (pintype "passive"))
    )
    (net (code "73") (name "unconnected-(SW4-S1-Pad2)") (class "Default")
      (node (ref "SW4") (pin "2") (pinfunction "S1_2") (pintype "passive"))
    )
    (net (code "74") (name "unconnected-(SW5-P1-Pad4)") (class "Default")
      (node (ref "SW5") (pin "4") (pinfunction "P1_4") (pintype "passive"))
    )
    (net (code "75") (name "unconnected-(SW5-S1-Pad2)") (class "Default")
      (node (ref "SW5") (pin "2") (pinfunction "S1_2") (pintype "passive"))
    )
    (net (code "76") (name "unconnected-(SW6-P1-Pad4)") (class "Default")
      (node (ref "SW6") (pin "4") (pinfunction "P1_4") (pintype "passive"))
    )
    (net (code "77") (name "unconnected-(SW6-S1-Pad2)") (class "Default")
      (node (ref "SW6") (pin "2") (pinfunction "S1_2") (pintype "passive"))
    )
    (net (code "78") (name "unconnected-(SW7-P1-Pad4)") (class "Default")
      (node (ref "SW7") (pin "4") (pinfunction "P1_4") (pintype "passive"))
    )
    (net (code "79") (name "unconnected-(SW7-S1-Pad2)") (class "Default")
      (node (ref "SW7") (pin "2") (pinfunction "S1_2") (pintype "passive"))
    )
    (net (code "80") (name "unconnected-(SW8-P1-Pad4)") (class "Default")
      (node (ref "SW8") (pin "4") (pinfunction "P1_4") (pintype "passive"))
    )
    (net (code "81") (name "unconnected-(SW8-S1-Pad2)") (class "Default")
      (node (ref "SW8") (pin "2") (pinfunction "S1_2") (pintype "passive"))
    )
    (net (code "82") (name "unconnected-(SW9-P1-Pad4)") (class "Default")
      (node (ref "SW9") (pin "4") (pinfunction "P1_4") (pintype "passive"))
    )
    (net (code "83") (name "unconnected-(SW9-S1-Pad2)") (class "Default")
      (node (ref "SW9") (pin "2") (pinfunction "S1_2") (pintype "passive"))
    )
  )
)
